# arduino_drivershield_1l.net
KiCad netlist of a schematic drawn in EAGLE
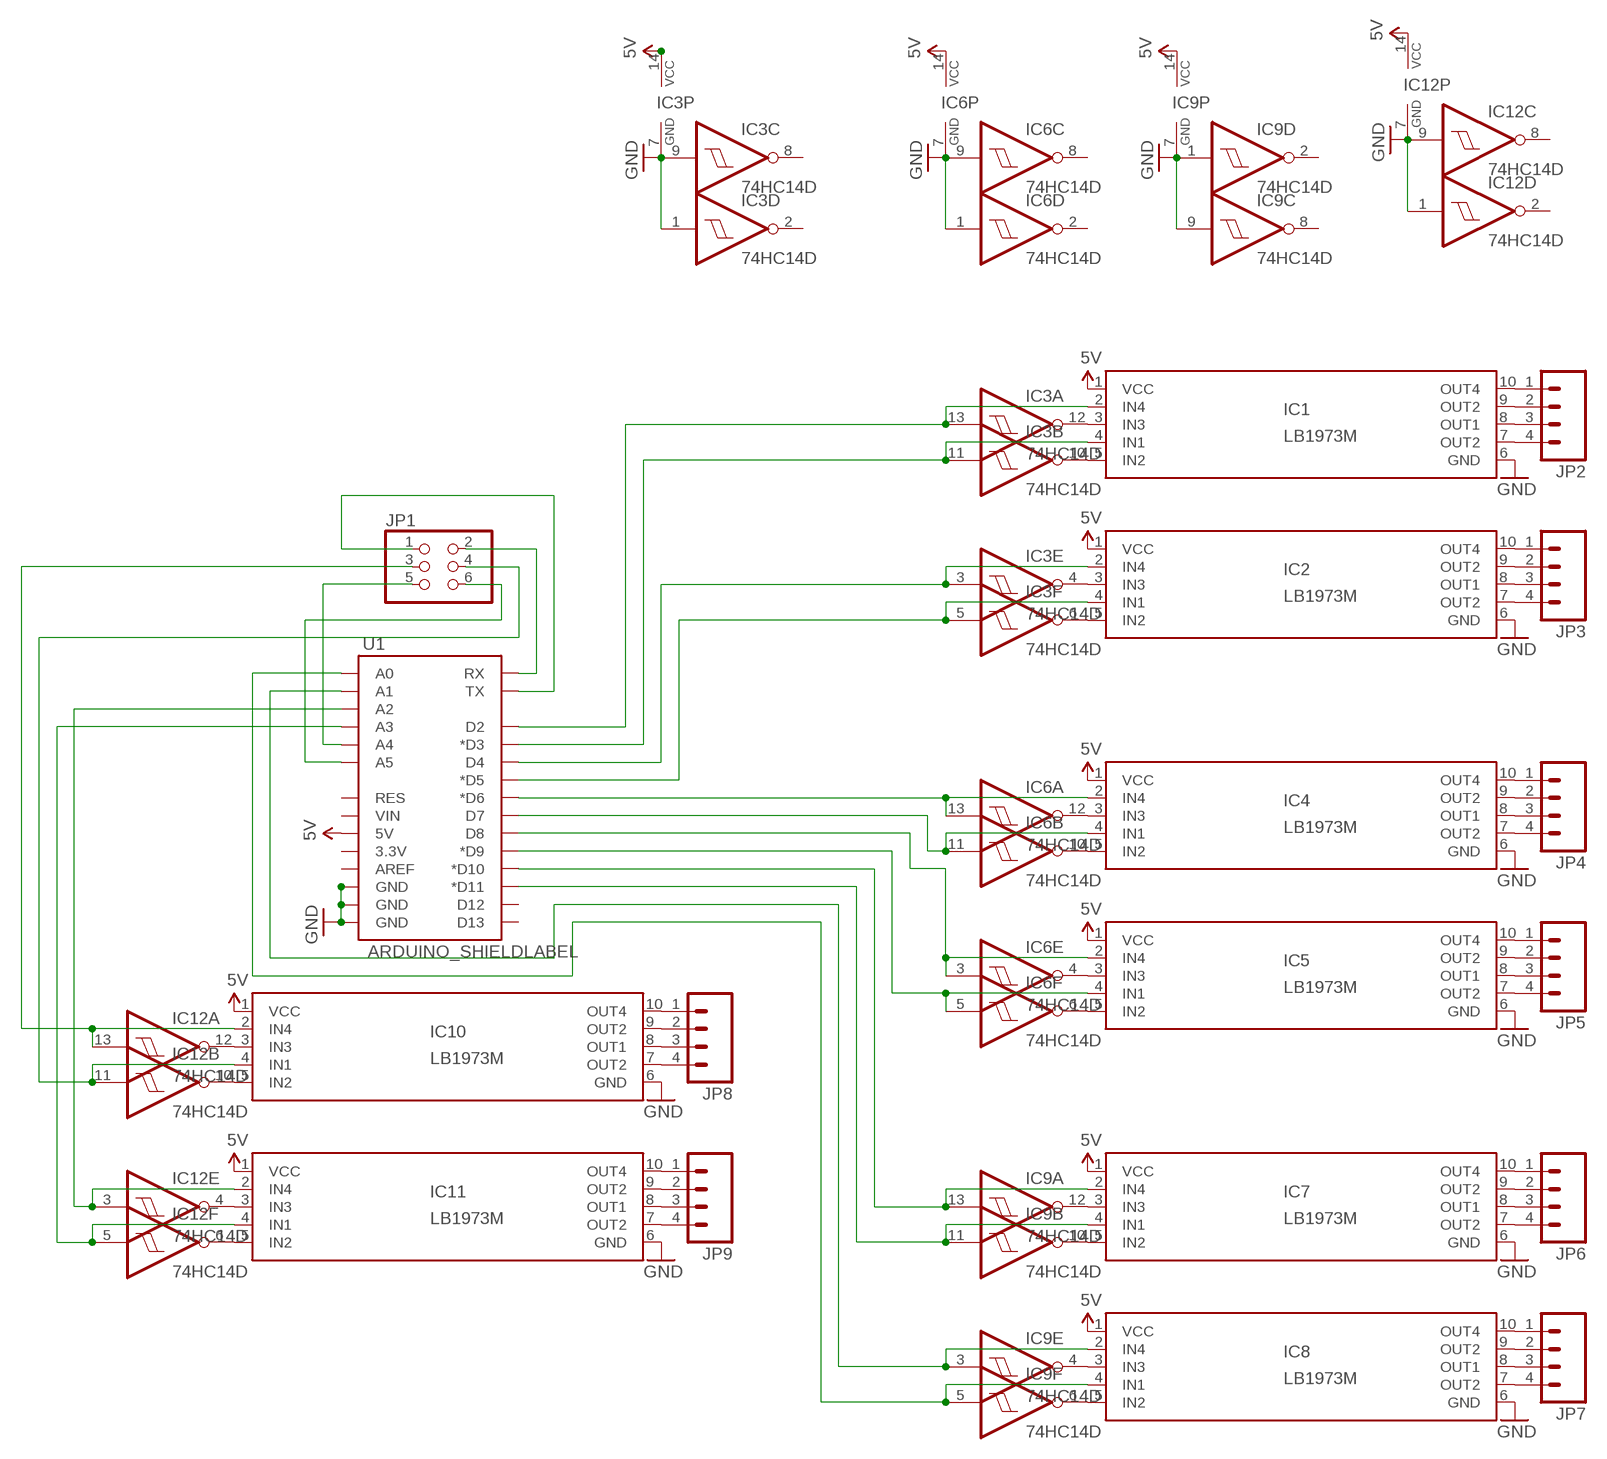
[diagram p0: schematic, sheet 1]

(export (version "E")
  (design (tool "Eeschema 10.0.6"))
  (components
    (comp (ref "IC1")
      (value "LB1973M")
      (footprint "eagle-import:SSOP10")
      (libsource (lib "eagle-import") (part "LB1973M"))
    )
    (comp (ref "IC2")
      (value "LB1973M")
      (footprint "eagle-import:SSOP10")
      (libsource (lib "eagle-import") (part "LB1973M"))
    )
    (comp (ref "IC3")
      (value "74HC14D")
      (footprint "eagle-import:SO14")
      (libsource (lib "eagle-import") (part "7414DHC"))
    )
    (comp (ref "IC4")
      (value "LB1973M")
      (footprint "eagle-import:SSOP10")
      (libsource (lib "eagle-import") (part "LB1973M"))
    )
    (comp (ref "IC5")
      (value "LB1973M")
      (footprint "eagle-import:SSOP10")
      (libsource (lib "eagle-import") (part "LB1973M"))
    )
    (comp (ref "IC6")
      (value "74HC14D")
      (footprint "eagle-import:SO14")
      (libsource (lib "eagle-import") (part "7414DHC"))
    )
    (comp (ref "IC7")
      (value "LB1973M")
      (footprint "eagle-import:SSOP10")
      (libsource (lib "eagle-import") (part "LB1973M"))
    )
    (comp (ref "IC8")
      (value "LB1973M")
      (footprint "eagle-import:SSOP10")
      (libsource (lib "eagle-import") (part "LB1973M"))
    )
    (comp (ref "IC9")
      (value "74HC14D")
      (footprint "eagle-import:SO14")
      (libsource (lib "eagle-import") (part "7414DHC"))
    )
    (comp (ref "IC10")
      (value "LB1973M")
      (footprint "eagle-import:SSOP10")
      (libsource (lib "eagle-import") (part "LB1973M"))
    )
    (comp (ref "IC11")
      (value "LB1973M")
      (footprint "eagle-import:SSOP10")
      (libsource (lib "eagle-import") (part "LB1973M"))
    )
    (comp (ref "IC12")
      (value "74HC14D")
      (footprint "eagle-import:SO14")
      (libsource (lib "eagle-import") (part "7414DHC"))
    )
    (comp (ref "JP1")
      (value "PINHD-2X3")
      (footprint "eagle-import:2X03")
      (libsource (lib "eagle-import") (part "PINHD-2X3"))
    )
    (comp (ref "JP2")
      (value "M041X04_NO_SILK")
      (footprint "eagle-import:1X04_NO_SILK")
      (libsource (lib "eagle-import") (part "M041X04_NO_SILK"))
    )
    (comp (ref "JP3")
      (value "M041X04_NO_SILK")
      (footprint "eagle-import:1X04_NO_SILK")
      (libsource (lib "eagle-import") (part "M041X04_NO_SILK"))
    )
    (comp (ref "JP4")
      (value "M041X04_NO_SILK")
      (footprint "eagle-import:1X04_NO_SILK")
      (libsource (lib "eagle-import") (part "M041X04_NO_SILK"))
    )
    (comp (ref "JP5")
      (value "M041X04_NO_SILK")
      (footprint "eagle-import:1X04_NO_SILK")
      (libsource (lib "eagle-import") (part "M041X04_NO_SILK"))
    )
    (comp (ref "JP6")
      (value "M041X04_NO_SILK")
      (footprint "eagle-import:1X04_NO_SILK")
      (libsource (lib "eagle-import") (part "M041X04_NO_SILK"))
    )
    (comp (ref "JP7")
      (value "M041X04_NO_SILK")
      (footprint "eagle-import:1X04_NO_SILK")
      (libsource (lib "eagle-import") (part "M041X04_NO_SILK"))
    )
    (comp (ref "JP8")
      (value "M041X04_NO_SILK")
      (footprint "eagle-import:1X04_NO_SILK")
      (libsource (lib "eagle-import") (part "M041X04_NO_SILK"))
    )
    (comp (ref "JP9")
      (value "M041X04_NO_SILK")
      (footprint "eagle-import:1X04_NO_SILK")
      (libsource (lib "eagle-import") (part "M041X04_NO_SILK"))
    )
    (comp (ref "U1")
      (value "ARDUINO_SHIELDLABEL")
      (footprint "eagle-import:DUEMILANOVE_SHIELD")
      (libsource (lib "eagle-import") (part "ARDUINO_SHIELDLABEL"))
    )
  )
  (nets
    (net (code "1") (name "5V") (class "Default")
      (node (ref "IC1") (pin "1") (pinfunction "VCC_1") (pintype "power_in"))
      (node (ref "IC10") (pin "1") (pinfunction "VCC_1") (pintype "power_in"))
      (node (ref "IC11") (pin "1") (pinfunction "VCC_1") (pintype "power_in"))
      (node (ref "IC12") (pin "14") (pinfunction "VCC_14") (pintype "power_in"))
      (node (ref "IC2") (pin "1") (pinfunction "VCC_1") (pintype "power_in"))
      (node (ref "IC3") (pin "14") (pinfunction "VCC_14") (pintype "power_in"))
      (node (ref "IC4") (pin "1") (pinfunction "VCC_1") (pintype "power_in"))
      (node (ref "IC5") (pin "1") (pinfunction "VCC_1") (pintype "power_in"))
      (node (ref "IC6") (pin "14") (pinfunction "VCC_14") (pintype "power_in"))
      (node (ref "IC7") (pin "1") (pinfunction "VCC_1") (pintype "power_in"))
      (node (ref "IC8") (pin "1") (pinfunction "VCC_1") (pintype "power_in"))
      (node (ref "IC9") (pin "14") (pinfunction "VCC_14") (pintype "power_in"))
      (node (ref "U1") (pin "5V") (pinfunction "5V_5V") (pintype "bidirectional"))
    )
    (net (code "2") (name "GND") (class "Default")
      (node (ref "IC1") (pin "6") (pinfunction "GND_6") (pintype "power_in"))
      (node (ref "IC10") (pin "6") (pinfunction "GND_6") (pintype "power_in"))
      (node (ref "IC11") (pin "6") (pinfunction "GND_6") (pintype "power_in"))
      (node (ref "IC12") (pin "1") (pinfunction "I_1") (pintype "input"))
      (node (ref "IC12") (pin "7") (pinfunction "GND_7") (pintype "power_in"))
      (node (ref "IC12") (pin "9") (pinfunction "I_9") (pintype "input"))
      (node (ref "IC2") (pin "6") (pinfunction "GND_6") (pintype "power_in"))
      (node (ref "IC3") (pin "1") (pinfunction "I_1") (pintype "input"))
      (node (ref "IC3") (pin "7") (pinfunction "GND_7") (pintype "power_in"))
      (node (ref "IC3") (pin "9") (pinfunction "I_9") (pintype "input"))
      (node (ref "IC4") (pin "6") (pinfunction "GND_6") (pintype "power_in"))
      (node (ref "IC5") (pin "6") (pinfunction "GND_6") (pintype "power_in"))
      (node (ref "IC6") (pin "1") (pinfunction "I_1") (pintype "input"))
      (node (ref "IC6") (pin "7") (pinfunction "GND_7") (pintype "power_in"))
      (node (ref "IC6") (pin "9") (pinfunction "I_9") (pintype "input"))
      (node (ref "IC7") (pin "6") (pinfunction "GND_6") (pintype "power_in"))
      (node (ref "IC8") (pin "6") (pinfunction "GND_6") (pintype "power_in"))
      (node (ref "IC9") (pin "1") (pinfunction "I_1") (pintype "input"))
      (node (ref "IC9") (pin "7") (pinfunction "GND_7") (pintype "power_in"))
      (node (ref "IC9") (pin "9") (pinfunction "I_9") (pintype "input"))
      (node (ref "U1") (pin "GND@0") (pinfunction "GND_GND@0") (pintype "bidirectional"))
      (node (ref "U1") (pin "GND@1") (pinfunction "GND_GND@1") (pintype "bidirectional"))
      (node (ref "U1") (pin "GND@2") (pinfunction "GND_GND@2") (pintype "bidirectional"))
    )
    (net (code "3") (name "Net-(IC1-IN1)") (class "Default")
      (node (ref "IC1") (pin "4") (pinfunction "IN1_4") (pintype "input"))
      (node (ref "IC3") (pin "11") (pinfunction "I_11") (pintype "input"))
      (node (ref "U1") (pin "D3") (pinfunction "*D3_D3") (pintype "bidirectional"))
    )
    (net (code "4") (name "Net-(IC1-IN2)") (class "Default")
      (node (ref "IC1") (pin "5") (pinfunction "IN2_5") (pintype "input"))
      (node (ref "IC3") (pin "10") (pinfunction "O_10") (pintype "output"))
    )
    (net (code "5") (name "Net-(IC1-IN3)") (class "Default")
      (node (ref "IC1") (pin "3") (pinfunction "IN3_3") (pintype "input"))
      (node (ref "IC3") (pin "12") (pinfunction "O_12") (pintype "output"))
    )
    (net (code "6") (name "Net-(IC1-IN4)") (class "Default")
      (node (ref "IC1") (pin "2") (pinfunction "IN4_2") (pintype "input"))
      (node (ref "IC3") (pin "13") (pinfunction "I_13") (pintype "input"))
      (node (ref "U1") (pin "D2") (pinfunction "D2_D2") (pintype "bidirectional"))
    )
    (net (code "7") (name "Net-(IC1-OUT1)") (class "Default")
      (node (ref "IC1") (pin "8") (pinfunction "OUT1_8") (pintype "output"))
      (node (ref "JP2") (pin "3") (pinfunction "3_3") (pintype "passive"))
    )
    (net (code "8") (name "Net-(IC1-OUT2-Pad7)") (class "Default")
      (node (ref "IC1") (pin "7") (pinfunction "OUT2_7") (pintype "output"))
      (node (ref "JP2") (pin "4") (pinfunction "4_4") (pintype "passive"))
    )
    (net (code "9") (name "Net-(IC1-OUT2-Pad9)") (class "Default")
      (node (ref "IC1") (pin "9") (pinfunction "OUT2_9") (pintype "output"))
      (node (ref "JP2") (pin "2") (pinfunction "2_2") (pintype "passive"))
    )
    (net (code "10") (name "Net-(IC1-OUT4)") (class "Default")
      (node (ref "IC1") (pin "10") (pinfunction "OUT4_10") (pintype "output"))
      (node (ref "JP2") (pin "1") (pinfunction "1_1") (pintype "passive"))
    )
    (net (code "11") (name "Net-(IC2-IN1)") (class "Default")
      (node (ref "IC2") (pin "4") (pinfunction "IN1_4") (pintype "input"))
      (node (ref "IC3") (pin "5") (pinfunction "I_5") (pintype "input"))
      (node (ref "U1") (pin "D5") (pinfunction "*D5_D5") (pintype "bidirectional"))
    )
    (net (code "12") (name "Net-(IC2-IN2)") (class "Default")
      (node (ref "IC2") (pin "5") (pinfunction "IN2_5") (pintype "input"))
      (node (ref "IC3") (pin "6") (pinfunction "O_6") (pintype "output"))
    )
    (net (code "13") (name "Net-(IC2-IN3)") (class "Default")
      (node (ref "IC2") (pin "3") (pinfunction "IN3_3") (pintype "input"))
      (node (ref "IC3") (pin "4") (pinfunction "O_4") (pintype "output"))
    )
    (net (code "14") (name "Net-(IC2-IN4)") (class "Default")
      (node (ref "IC2") (pin "2") (pinfunction "IN4_2") (pintype "input"))
      (node (ref "IC3") (pin "3") (pinfunction "I_3") (pintype "input"))
      (node (ref "U1") (pin "D4") (pinfunction "D4_D4") (pintype "bidirectional"))
    )
    (net (code "15") (name "Net-(IC2-OUT1)") (class "Default")
      (node (ref "IC2") (pin "8") (pinfunction "OUT1_8") (pintype "output"))
      (node (ref "JP3") (pin "3") (pinfunction "3_3") (pintype "passive"))
    )
    (net (code "16") (name "Net-(IC2-OUT2-Pad7)") (class "Default")
      (node (ref "IC2") (pin "7") (pinfunction "OUT2_7") (pintype "output"))
      (node (ref "JP3") (pin "4") (pinfunction "4_4") (pintype "passive"))
    )
    (net (code "17") (name "Net-(IC2-OUT2-Pad9)") (class "Default")
      (node (ref "IC2") (pin "9") (pinfunction "OUT2_9") (pintype "output"))
      (node (ref "JP3") (pin "2") (pinfunction "2_2") (pintype "passive"))
    )
    (net (code "18") (name "Net-(IC2-OUT4)") (class "Default")
      (node (ref "IC2") (pin "10") (pinfunction "OUT4_10") (pintype "output"))
      (node (ref "JP3") (pin "1") (pinfunction "1_1") (pintype "passive"))
    )
    (net (code "19") (name "Net-(IC4-IN1)") (class "Default")
      (node (ref "IC4") (pin "4") (pinfunction "IN1_4") (pintype "input"))
      (node (ref "IC6") (pin "11") (pinfunction "I_11") (pintype "input"))
      (node (ref "U1") (pin "D7") (pinfunction "D7_D7") (pintype "bidirectional"))
    )
    (net (code "20") (name "Net-(IC4-IN2)") (class "Default")
      (node (ref "IC4") (pin "5") (pinfunction "IN2_5") (pintype "input"))
      (node (ref "IC6") (pin "10") (pinfunction "O_10") (pintype "output"))
    )
    (net (code "21") (name "Net-(IC4-IN3)") (class "Default")
      (node (ref "IC4") (pin "3") (pinfunction "IN3_3") (pintype "input"))
      (node (ref "IC6") (pin "12") (pinfunction "O_12") (pintype "output"))
    )
    (net (code "22") (name "Net-(IC4-IN4)") (class "Default")
      (node (ref "IC4") (pin "2") (pinfunction "IN4_2") (pintype "input"))
      (node (ref "IC6") (pin "13") (pinfunction "I_13") (pintype "input"))
      (node (ref "U1") (pin "D6") (pinfunction "*D6_D6") (pintype "bidirectional"))
    )
    (net (code "23") (name "Net-(IC4-OUT1)") (class "Default")
      (node (ref "IC4") (pin "8") (pinfunction "OUT1_8") (pintype "output"))
      (node (ref "JP4") (pin "3") (pinfunction "3_3") (pintype "passive"))
    )
    (net (code "24") (name "Net-(IC4-OUT2-Pad7)") (class "Default")
      (node (ref "IC4") (pin "7") (pinfunction "OUT2_7") (pintype "output"))
      (node (ref "JP4") (pin "4") (pinfunction "4_4") (pintype "passive"))
    )
    (net (code "25") (name "Net-(IC4-OUT2-Pad9)") (class "Default")
      (node (ref "IC4") (pin "9") (pinfunction "OUT2_9") (pintype "output"))
      (node (ref "JP4") (pin "2") (pinfunction "2_2") (pintype "passive"))
    )
    (net (code "26") (name "Net-(IC4-OUT4)") (class "Default")
      (node (ref "IC4") (pin "10") (pinfunction "OUT4_10") (pintype "output"))
      (node (ref "JP4") (pin "1") (pinfunction "1_1") (pintype "passive"))
    )
    (net (code "27") (name "Net-(IC5-IN1)") (class "Default")
      (node (ref "IC5") (pin "4") (pinfunction "IN1_4") (pintype "input"))
      (node (ref "IC6") (pin "5") (pinfunction "I_5") (pintype "input"))
      (node (ref "U1") (pin "D9") (pinfunction "*D9_D9") (pintype "bidirectional"))
    )
    (net (code "28") (name "Net-(IC5-IN2)") (class "Default")
      (node (ref "IC5") (pin "5") (pinfunction "IN2_5") (pintype "input"))
      (node (ref "IC6") (pin "6") (pinfunction "O_6") (pintype "output"))
    )
    (net (code "29") (name "Net-(IC5-IN3)") (class "Default")
      (node (ref "IC5") (pin "3") (pinfunction "IN3_3") (pintype "input"))
      (node (ref "IC6") (pin "4") (pinfunction "O_4") (pintype "output"))
    )
    (net (code "30") (name "Net-(IC5-IN4)") (class "Default")
      (node (ref "IC5") (pin "2") (pinfunction "IN4_2") (pintype "input"))
      (node (ref "IC6") (pin "3") (pinfunction "I_3") (pintype "input"))
      (node (ref "U1") (pin "D8") (pinfunction "D8_D8") (pintype "bidirectional"))
    )
    (net (code "31") (name "Net-(IC5-OUT1)") (class "Default")
      (node (ref "IC5") (pin "8") (pinfunction "OUT1_8") (pintype "output"))
      (node (ref "JP5") (pin "3") (pinfunction "3_3") (pintype "passive"))
    )
    (net (code "32") (name "Net-(IC5-OUT2-Pad7)") (class "Default")
      (node (ref "IC5") (pin "7") (pinfunction "OUT2_7") (pintype "output"))
      (node (ref "JP5") (pin "4") (pinfunction "4_4") (pintype "passive"))
    )
    (net (code "33") (name "Net-(IC5-OUT2-Pad9)") (class "Default")
      (node (ref "IC5") (pin "9") (pinfunction "OUT2_9") (pintype "output"))
      (node (ref "JP5") (pin "2") (pinfunction "2_2") (pintype "passive"))
    )
    (net (code "34") (name "Net-(IC5-OUT4)") (class "Default")
      (node (ref "IC5") (pin "10") (pinfunction "OUT4_10") (pintype "output"))
      (node (ref "JP5") (pin "1") (pinfunction "1_1") (pintype "passive"))
    )
    (net (code "35") (name "Net-(IC7-IN1)") (class "Default")
      (node (ref "IC7") (pin "4") (pinfunction "IN1_4") (pintype "input"))
      (node (ref "IC9") (pin "11") (pinfunction "I_11") (pintype "input"))
      (node (ref "U1") (pin "D11") (pinfunction "*D11_D11") (pintype "bidirectional"))
    )
    (net (code "36") (name "Net-(IC7-IN2)") (class "Default")
      (node (ref "IC7") (pin "5") (pinfunction "IN2_5") (pintype "input"))
      (node (ref "IC9") (pin "10") (pinfunction "O_10") (pintype "output"))
    )
    (net (code "37") (name "Net-(IC7-IN3)") (class "Default")
      (node (ref "IC7") (pin "3") (pinfunction "IN3_3") (pintype "input"))
      (node (ref "IC9") (pin "12") (pinfunction "O_12") (pintype "output"))
    )
    (net (code "38") (name "Net-(IC7-IN4)") (class "Default")
      (node (ref "IC7") (pin "2") (pinfunction "IN4_2") (pintype "input"))
      (node (ref "IC9") (pin "13") (pinfunction "I_13") (pintype "input"))
      (node (ref "U1") (pin "D10") (pinfunction "*D10_D10") (pintype "bidirectional"))
    )
    (net (code "39") (name "Net-(IC7-OUT1)") (class "Default")
      (node (ref "IC7") (pin "8") (pinfunction "OUT1_8") (pintype "output"))
      (node (ref "JP6") (pin "3") (pinfunction "3_3") (pintype "passive"))
    )
    (net (code "40") (name "Net-(IC7-OUT2-Pad7)") (class "Default")
      (node (ref "IC7") (pin "7") (pinfunction "OUT2_7") (pintype "output"))
      (node (ref "JP6") (pin "4") (pinfunction "4_4") (pintype "passive"))
    )
    (net (code "41") (name "Net-(IC7-OUT2-Pad9)") (class "Default")
      (node (ref "IC7") (pin "9") (pinfunction "OUT2_9") (pintype "output"))
      (node (ref "JP6") (pin "2") (pinfunction "2_2") (pintype "passive"))
    )
    (net (code "42") (name "Net-(IC7-OUT4)") (class "Default")
      (node (ref "IC7") (pin "10") (pinfunction "OUT4_10") (pintype "output"))
      (node (ref "JP6") (pin "1") (pinfunction "1_1") (pintype "passive"))
    )
    (net (code "43") (name "Net-(IC8-IN1)") (class "Default")
      (node (ref "IC8") (pin "4") (pinfunction "IN1_4") (pintype "input"))
      (node (ref "IC9") (pin "5") (pinfunction "I_5") (pintype "input"))
      (node (ref "U1") (pin "A0") (pinfunction "A0_A0") (pintype "bidirectional"))
    )
    (net (code "44") (name "Net-(IC8-IN2)") (class "Default")
      (node (ref "IC8") (pin "5") (pinfunction "IN2_5") (pintype "input"))
      (node (ref "IC9") (pin "6") (pinfunction "O_6") (pintype "output"))
    )
    (net (code "45") (name "Net-(IC8-IN3)") (class "Default")
      (node (ref "IC8") (pin "3") (pinfunction "IN3_3") (pintype "input"))
      (node (ref "IC9") (pin "4") (pinfunction "O_4") (pintype "output"))
    )
    (net (code "46") (name "Net-(IC8-IN4)") (class "Default")
      (node (ref "IC8") (pin "2") (pinfunction "IN4_2") (pintype "input"))
      (node (ref "IC9") (pin "3") (pinfunction "I_3") (pintype "input"))
      (node (ref "U1") (pin "A1") (pinfunction "A1_A1") (pintype "bidirectional"))
    )
    (net (code "47") (name "Net-(IC8-OUT1)") (class "Default")
      (node (ref "IC8") (pin "8") (pinfunction "OUT1_8") (pintype "output"))
      (node (ref "JP7") (pin "3") (pinfunction "3_3") (pintype "passive"))
    )
    (net (code "48") (name "Net-(IC8-OUT2-Pad7)") (class "Default")
      (node (ref "IC8") (pin "7") (pinfunction "OUT2_7") (pintype "output"))
      (node (ref "JP7") (pin "4") (pinfunction "4_4") (pintype "passive"))
    )
    (net (code "49") (name "Net-(IC8-OUT2-Pad9)") (class "Default")
      (node (ref "IC8") (pin "9") (pinfunction "OUT2_9") (pintype "output"))
      (node (ref "JP7") (pin "2") (pinfunction "2_2") (pintype "passive"))
    )
    (net (code "50") (name "Net-(IC8-OUT4)") (class "Default")
      (node (ref "IC8") (pin "10") (pinfunction "OUT4_10") (pintype "output"))
      (node (ref "JP7") (pin "1") (pinfunction "1_1") (pintype "passive"))
    )
    (net (code "51") (name "Net-(IC10-IN1)") (class "Default")
      (node (ref "IC10") (pin "4") (pinfunction "IN1_4") (pintype "input"))
      (node (ref "IC12") (pin "11") (pinfunction "I_11") (pintype "input"))
      (node (ref "JP1") (pin "4") (pinfunction "4_4") (pintype "passive"))
    )
    (net (code "52") (name "Net-(IC10-IN2)") (class "Default")
      (node (ref "IC10") (pin "5") (pinfunction "IN2_5") (pintype "input"))
      (node (ref "IC12") (pin "10") (pinfunction "O_10") (pintype "output"))
    )
    (net (code "53") (name "Net-(IC10-IN3)") (class "Default")
      (node (ref "IC10") (pin "3") (pinfunction "IN3_3") (pintype "input"))
      (node (ref "IC12") (pin "12") (pinfunction "O_12") (pintype "output"))
    )
    (net (code "54") (name "Net-(IC10-IN4)") (class "Default")
      (node (ref "IC10") (pin "2") (pinfunction "IN4_2") (pintype "input"))
      (node (ref "IC12") (pin "13") (pinfunction "I_13") (pintype "input"))
      (node (ref "JP1") (pin "3") (pinfunction "3_3") (pintype "passive"))
    )
    (net (code "55") (name "Net-(IC10-OUT1)") (class "Default")
      (node (ref "IC10") (pin "8") (pinfunction "OUT1_8") (pintype "output"))
      (node (ref "JP8") (pin "3") (pinfunction "3_3") (pintype "passive"))
    )
    (net (code "56") (name "Net-(IC10-OUT2-Pad7)") (class "Default")
      (node (ref "IC10") (pin "7") (pinfunction "OUT2_7") (pintype "output"))
      (node (ref "JP8") (pin "4") (pinfunction "4_4") (pintype "passive"))
    )
    (net (code "57") (name "Net-(IC10-OUT2-Pad9)") (class "Default")
      (node (ref "IC10") (pin "9") (pinfunction "OUT2_9") (pintype "output"))
      (node (ref "JP8") (pin "2") (pinfunction "2_2") (pintype "passive"))
    )
    (net (code "58") (name "Net-(IC10-OUT4)") (class "Default")
      (node (ref "IC10") (pin "10") (pinfunction "OUT4_10") (pintype "output"))
      (node (ref "JP8") (pin "1") (pinfunction "1_1") (pintype "passive"))
    )
    (net (code "59") (name "Net-(IC11-IN1)") (class "Default")
      (node (ref "IC11") (pin "4") (pinfunction "IN1_4") (pintype "input"))
      (node (ref "IC12") (pin "5") (pinfunction "I_5") (pintype "input"))
      (node (ref "U1") (pin "A3") (pinfunction "A3_A3") (pintype "bidirectional"))
    )
    (net (code "60") (name "Net-(IC11-IN2)") (class "Default")
      (node (ref "IC11") (pin "5") (pinfunction "IN2_5") (pintype "input"))
      (node (ref "IC12") (pin "6") (pinfunction "O_6") (pintype "output"))
    )
    (net (code "61") (name "Net-(IC11-IN3)") (class "Default")
      (node (ref "IC11") (pin "3") (pinfunction "IN3_3") (pintype "input"))
      (node (ref "IC12") (pin "4") (pinfunction "O_4") (pintype "output"))
    )
    (net (code "62") (name "Net-(IC11-IN4)") (class "Default")
      (node (ref "IC11") (pin "2") (pinfunction "IN4_2") (pintype "input"))
      (node (ref "IC12") (pin "3") (pinfunction "I_3") (pintype "input"))
      (node (ref "U1") (pin "A2") (pinfunction "A2_A2") (pintype "bidirectional"))
    )
    (net (code "63") (name "Net-(IC11-OUT1)") (class "Default")
      (node (ref "IC11") (pin "8") (pinfunction "OUT1_8") (pintype "output"))
      (node (ref "JP9") (pin "3") (pinfunction "3_3") (pintype "passive"))
    )
    (net (code "64") (name "Net-(IC11-OUT2-Pad7)") (class "Default")
      (node (ref "IC11") (pin "7") (pinfunction "OUT2_7") (pintype "output"))
      (node (ref "JP9") (pin "4") (pinfunction "4_4") (pintype "passive"))
    )
    (net (code "65") (name "Net-(IC11-OUT2-Pad9)") (class "Default")
      (node (ref "IC11") (pin "9") (pinfunction "OUT2_9") (pintype "output"))
      (node (ref "JP9") (pin "2") (pinfunction "2_2") (pintype "passive"))
    )
    (net (code "66") (name "Net-(IC11-OUT4)") (class "Default")
      (node (ref "IC11") (pin "10") (pinfunction "OUT4_10") (pintype "output"))
      (node (ref "JP9") (pin "1") (pinfunction "1_1") (pintype "passive"))
    )
    (net (code "67") (name "Net-(JP1-Pad1)") (class "Default")
      (node (ref "JP1") (pin "1") (pinfunction "1_1") (pintype "passive"))
      (node (ref "U1") (pin "TX") (pinfunction "TX_TX") (pintype "bidirectional"))
    )
    (net (code "68") (name "Net-(JP1-Pad2)") (class "Default")
      (node (ref "JP1") (pin "2") (pinfunction "2_2") (pintype "passive"))
      (node (ref "U1") (pin "RX") (pinfunction "RX_RX") (pintype "bidirectional"))
    )
    (net (code "69") (name "Net-(JP1-Pad5)") (class "Default")
      (node (ref "JP1") (pin "5") (pinfunction "5_5") (pintype "passive"))
      (node (ref "U1") (pin "A4") (pinfunction "A4_A4") (pintype "bidirectional"))
    )
    (net (code "70") (name "Net-(JP1-Pad6)") (class "Default")
      (node (ref "JP1") (pin "6") (pinfunction "6_6") (pintype "passive"))
      (node (ref "U1") (pin "A5") (pinfunction "A5_A5") (pintype "bidirectional"))
    )
    (net (code "71") (name "unconnected-(IC3C-O-Pad8)") (class "Default")
      (node (ref "IC3") (pin "8") (pinfunction "O_8") (pintype "output"))
    )
    (net (code "72") (name "unconnected-(IC3D-O-Pad2)") (class "Default")
      (node (ref "IC3") (pin "2") (pinfunction "O_2") (pintype "output"))
    )
    (net (code "73") (name "unconnected-(IC6C-O-Pad8)") (class "Default")
      (node (ref "IC6") (pin "8") (pinfunction "O_8") (pintype "output"))
    )
    (net (code "74") (name "unconnected-(IC6D-O-Pad2)") (class "Default")
      (node (ref "IC6") (pin "2") (pinfunction "O_2") (pintype "output"))
    )
    (net (code "75") (name "unconnected-(IC9C-O-Pad8)") (class "Default")
      (node (ref "IC9") (pin "8") (pinfunction "O_8") (pintype "output"))
    )
    (net (code "76") (name "unconnected-(IC9D-O-Pad2)") (class "Default")
      (node (ref "IC9") (pin "2") (pinfunction "O_2") (pintype "output"))
    )
    (net (code "77") (name "unconnected-(IC12C-O-Pad8)") (class "Default")
      (node (ref "IC12") (pin "8") (pinfunction "O_8") (pintype "output"))
    )
    (net (code "78") (name "unconnected-(IC12D-O-Pad2)") (class "Default")
      (node (ref "IC12") (pin "2") (pinfunction "O_2") (pintype "output"))
    )
    (net (code "79") (name "unconnected-(U1-Pad3.3V)") (class "Default")
      (node (ref "U1") (pin "3.3V") (pinfunction "3.3V_3.3V") (pintype "bidirectional"))
    )
    (net (code "80") (name "unconnected-(U1-PadAREF)") (class "Default")
      (node (ref "U1") (pin "AREF") (pinfunction "AREF_AREF") (pintype "bidirectional"))
    )
    (net (code "81") (name "unconnected-(U1-PadD12)") (class "Default")
      (node (ref "U1") (pin "D12") (pinfunction "D12_D12") (pintype "bidirectional"))
    )
    (net (code "82") (name "unconnected-(U1-PadD13)") (class "Default")
      (node (ref "U1") (pin "D13") (pinfunction "D13_D13") (pintype "bidirectional"))
    )
    (net (code "83") (name "unconnected-(U1-PadRES)") (class "Default")
      (node (ref "U1") (pin "RES") (pinfunction "RES_RES") (pintype "bidirectional"))
    )
    (net (code "84") (name "unconnected-(U1-PadVIN)") (class "Default")
      (node (ref "U1") (pin "VIN") (pinfunction "VIN_VIN") (pintype "bidirectional"))
    )
  )
)
